# Proiect.net
KiCad netlist of a schematic drawn in EAGLE
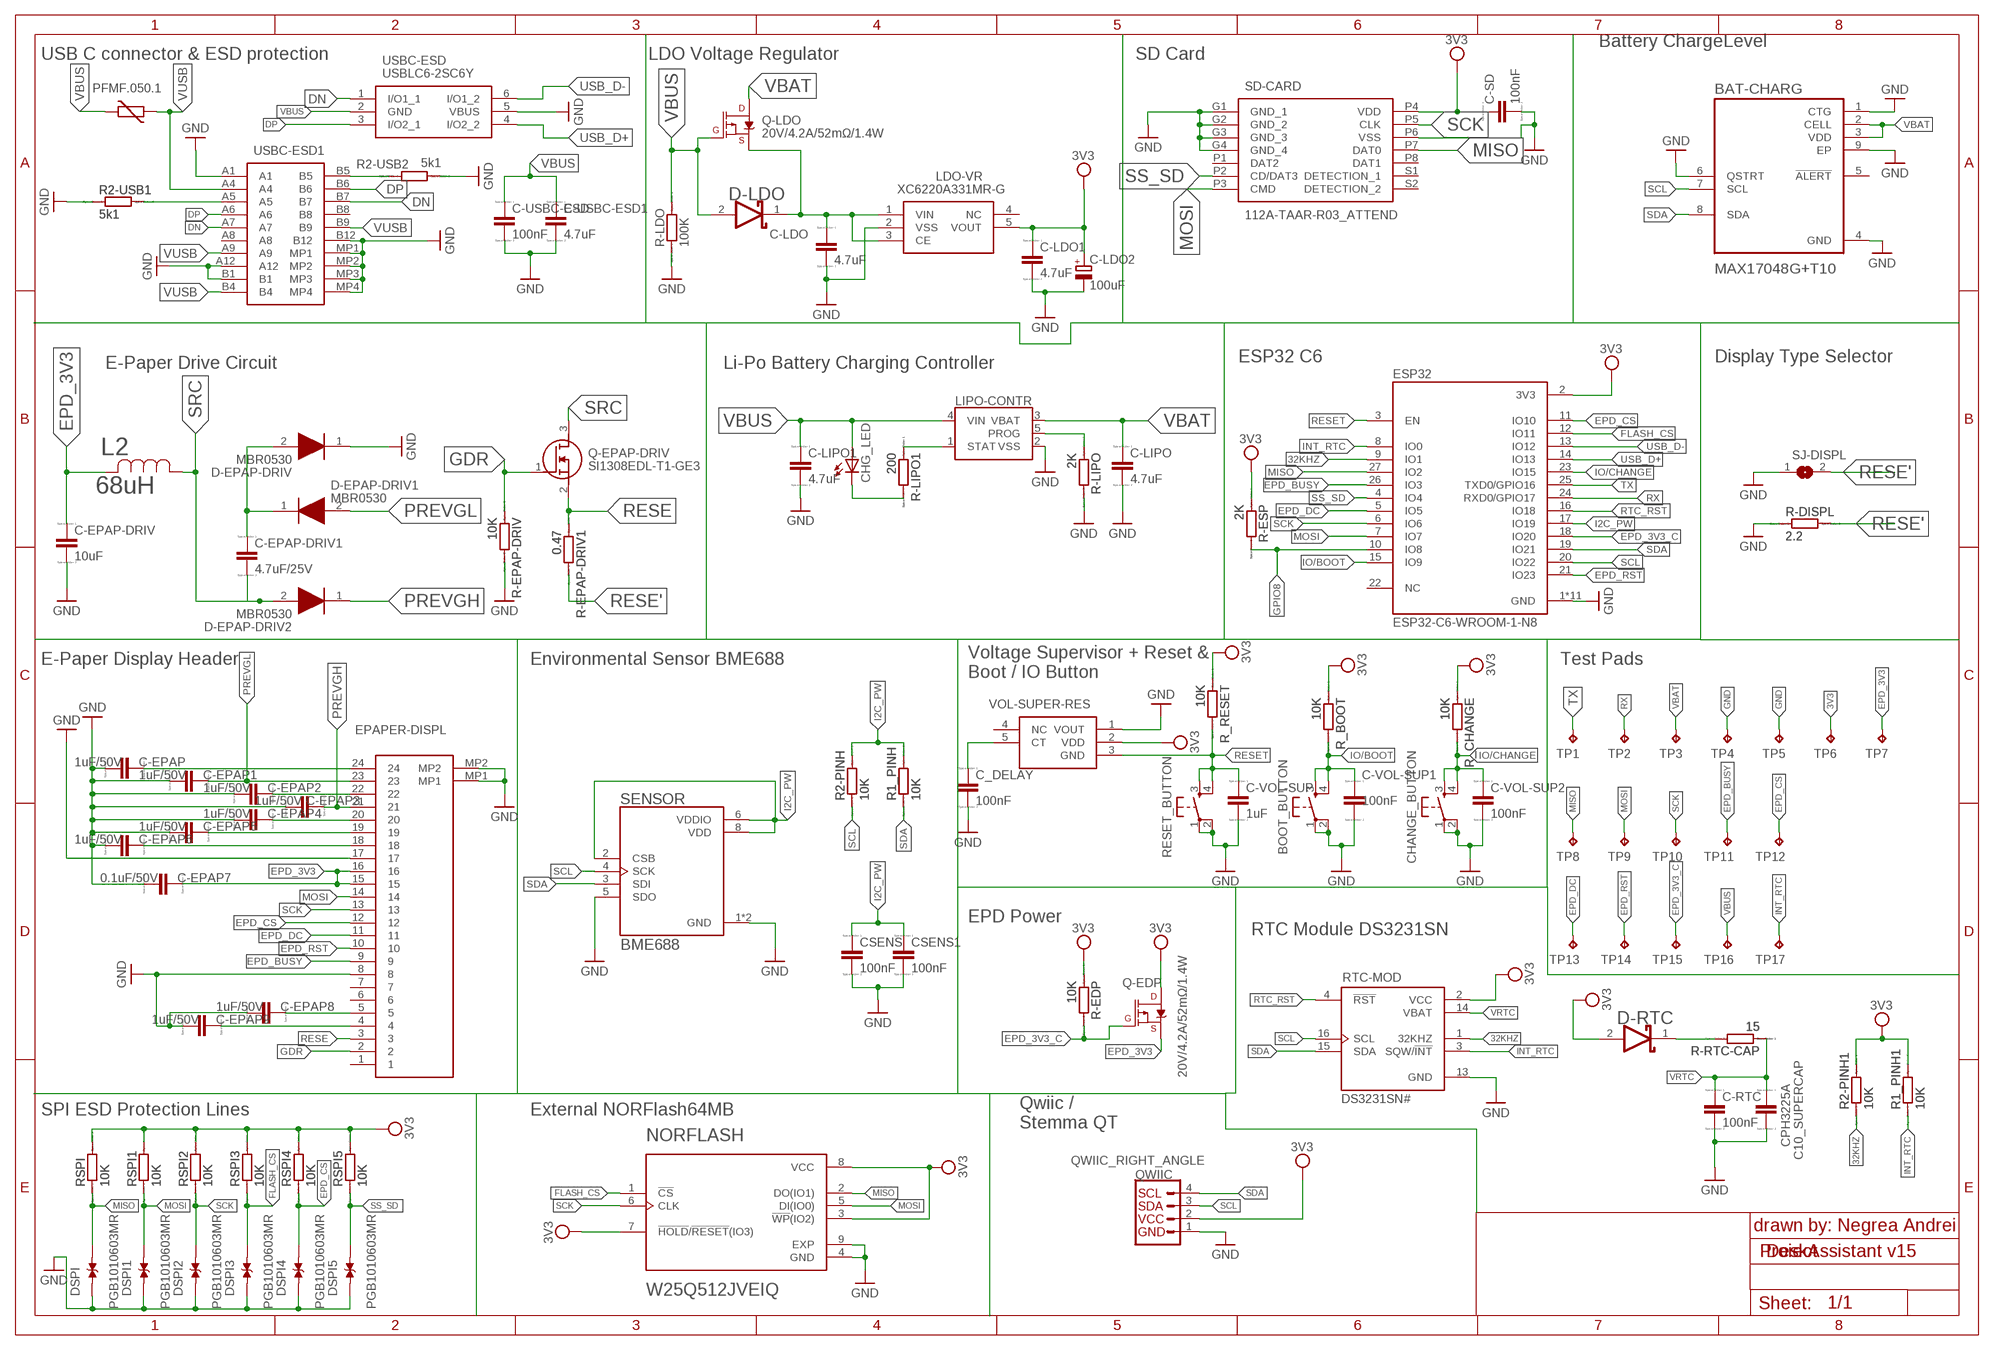
[diagram p0: schematic, sheet 1]

(export (version "E")
  (design (tool "Eeschema 10.0.6"))
  (components
    (comp (ref "BAT-CHARG")
      (value "MAX17048G+T10")
      (footprint "eagle-import:SON50P200X200X80-9N")
      (fields (field (name "MF") "Analog Devices"))
      (libsource (lib "eagle-import") (part "MAX17048G+T10"))
    )
    (comp (ref "BOOT_BUTTON")
      (value "BOOT_BUTTON")
      (footprint "eagle-import:MYBUTTON")
      (libsource (lib "eagle-import") (part "BUTTON_CUSYOMV1"))
    )
    (comp (ref "C-EPAP")
      (value "1uF/50V")
      (footprint "eagle-import:ESP32_WROVER_EAGLE-LTSPICE_C0402")
      (libsource (lib "eagle-import") (part "ESP32_WROVER_EAGLE-LTSPICE_CC0402"))
    )
    (comp (ref "C-EPAP-DRIV")
      (value "10uF")
      (footprint "eagle-import:ESP32_WROVER_EAGLE-LTSPICE_C0402")
      (libsource (lib "eagle-import") (part "ESP32_WROVER_EAGLE-LTSPICE_CC0402"))
    )
    (comp (ref "C-EPAP-DRIV1")
      (value "4.7uF/25V")
      (footprint "eagle-import:ESP32_WROVER_EAGLE-LTSPICE_C0402")
      (libsource (lib "eagle-import") (part "ESP32_WROVER_EAGLE-LTSPICE_CC0402"))
    )
    (comp (ref "C-EPAP1")
      (value "1uF/50V")
      (footprint "eagle-import:ESP32_WROVER_EAGLE-LTSPICE_C0402")
      (libsource (lib "eagle-import") (part "ESP32_WROVER_EAGLE-LTSPICE_CC0402"))
    )
    (comp (ref "C-EPAP2")
      (value "1uF/50V")
      (footprint "eagle-import:ESP32_WROVER_EAGLE-LTSPICE_C0402")
      (libsource (lib "eagle-import") (part "ESP32_WROVER_EAGLE-LTSPICE_CC0402"))
    )
    (comp (ref "C-EPAP3")
      (value "1uF/50V")
      (footprint "eagle-import:ESP32_WROVER_EAGLE-LTSPICE_C0402")
      (libsource (lib "eagle-import") (part "ESP32_WROVER_EAGLE-LTSPICE_CC0402"))
    )
    (comp (ref "C-EPAP4")
      (value "1uF/50V")
      (footprint "eagle-import:ESP32_WROVER_EAGLE-LTSPICE_C0402")
      (libsource (lib "eagle-import") (part "ESP32_WROVER_EAGLE-LTSPICE_CC0402"))
    )
    (comp (ref "C-EPAP5")
      (value "1uF/50V")
      (footprint "eagle-import:ESP32_WROVER_EAGLE-LTSPICE_C0402")
      (libsource (lib "eagle-import") (part "ESP32_WROVER_EAGLE-LTSPICE_CC0402"))
    )
    (comp (ref "C-EPAP6")
      (value "1uF/50V")
      (footprint "eagle-import:ESP32_WROVER_EAGLE-LTSPICE_C0402")
      (libsource (lib "eagle-import") (part "ESP32_WROVER_EAGLE-LTSPICE_CC0402"))
    )
    (comp (ref "C-EPAP7")
      (value "0.1uF/50V")
      (footprint "eagle-import:ESP32_WROVER_EAGLE-LTSPICE_C0402")
      (libsource (lib "eagle-import") (part "ESP32_WROVER_EAGLE-LTSPICE_CC0402"))
    )
    (comp (ref "C-EPAP8")
      (value "1uF/50V")
      (footprint "eagle-import:ESP32_WROVER_EAGLE-LTSPICE_C0402")
      (libsource (lib "eagle-import") (part "ESP32_WROVER_EAGLE-LTSPICE_CC0402"))
    )
    (comp (ref "C-EPAP9")
      (value "1uF/50V")
      (footprint "eagle-import:ESP32_WROVER_EAGLE-LTSPICE_C0402")
      (libsource (lib "eagle-import") (part "ESP32_WROVER_EAGLE-LTSPICE_CC0402"))
    )
    (comp (ref "C-LDO")
      (value "4.7uF")
      (footprint "eagle-import:ESP32_WROVER_EAGLE-LTSPICE_C0402")
      (libsource (lib "eagle-import") (part "ESP32_WROVER_EAGLE-LTSPICE_CC0402"))
    )
    (comp (ref "C-LDO1")
      (value "4.7uF")
      (footprint "eagle-import:ESP32_WROVER_EAGLE-LTSPICE_C0402")
      (libsource (lib "eagle-import") (part "ESP32_WROVER_EAGLE-LTSPICE_CC0402"))
    )
    (comp (ref "C-LDO2")
      (value "100uF")
      (footprint "eagle-import:RCL_CT3528")
      (libsource (lib "eagle-import") (part "RCL_CPOL-EUCT3528"))
    )
    (comp (ref "C-LIPO")
      (value "4.7uF")
      (footprint "eagle-import:ESP32_WROVER_EAGLE-LTSPICE_C0402")
      (libsource (lib "eagle-import") (part "ESP32_WROVER_EAGLE-LTSPICE_CC0402"))
    )
    (comp (ref "C-LIPO1")
      (value "4.7uF")
      (footprint "eagle-import:ESP32_WROVER_EAGLE-LTSPICE_C0402")
      (libsource (lib "eagle-import") (part "ESP32_WROVER_EAGLE-LTSPICE_CC0402"))
    )
    (comp (ref "C-RTC")
      (value "100nF")
      (footprint "eagle-import:ESP32_WROVER_EAGLE-LTSPICE_C0402")
      (libsource (lib "eagle-import") (part "ESP32_WROVER_EAGLE-LTSPICE_CC0402"))
    )
    (comp (ref "C-SD")
      (value "100nF")
      (footprint "eagle-import:ESP32_WROVER_EAGLE-LTSPICE_C0402")
      (libsource (lib "eagle-import") (part "ESP32_WROVER_EAGLE-LTSPICE_CC0402"))
    )
    (comp (ref "C-USBC-ESD")
      (value "100nF")
      (footprint "eagle-import:ESP32_WROVER_EAGLE-LTSPICE_C0402")
      (libsource (lib "eagle-import") (part "ESP32_WROVER_EAGLE-LTSPICE_CC0402"))
    )
    (comp (ref "C-USBC-ESD1")
      (value "4.7uF")
      (footprint "eagle-import:ESP32_WROVER_EAGLE-LTSPICE_C0402")
      (libsource (lib "eagle-import") (part "ESP32_WROVER_EAGLE-LTSPICE_CC0402"))
    )
    (comp (ref "C-VOL-SUP")
      (value "1uF")
      (footprint "eagle-import:ESP32_WROVER_EAGLE-LTSPICE_C0402")
      (libsource (lib "eagle-import") (part "ESP32_WROVER_EAGLE-LTSPICE_CC0402"))
    )
    (comp (ref "C-VOL-SUP1")
      (value "100nF")
      (footprint "eagle-import:ESP32_WROVER_EAGLE-LTSPICE_C0402")
      (libsource (lib "eagle-import") (part "ESP32_WROVER_EAGLE-LTSPICE_CC0402"))
    )
    (comp (ref "C-VOL-SUP2")
      (value "100nF")
      (footprint "eagle-import:ESP32_WROVER_EAGLE-LTSPICE_C0402")
      (libsource (lib "eagle-import") (part "ESP32_WROVER_EAGLE-LTSPICE_CC0402"))
    )
    (comp (ref "CHANGE_BUTTON")
      (value "CHANGE_BUTTON")
      (footprint "eagle-import:MYBUTTON")
      (libsource (lib "eagle-import") (part "BUTTON_CUSYOMV1"))
    )
    (comp (ref "CHG_LED")
      (value "ADAFRUIT_LEDCHIP-LED0603")
      (footprint "eagle-import:ADAFRUIT_CHIP-LED0603")
      (libsource (lib "eagle-import") (part "ADAFRUIT_LEDCHIP-LED0603"))
    )
    (comp (ref "CPH3225A")
      (value "C10_SUPERCAP")
      (footprint "eagle-import:ESP32_WROVER_EAGLE-LTSPICE_C0402")
      (libsource (lib "eagle-import") (part "ESP32_WROVER_EAGLE-LTSPICE_CC0402"))
    )
    (comp (ref "CSENS")
      (value "100nF")
      (footprint "eagle-import:ESP32_WROVER_EAGLE-LTSPICE_C0402")
      (libsource (lib "eagle-import") (part "ESP32_WROVER_EAGLE-LTSPICE_CC0402"))
    )
    (comp (ref "CSENS1")
      (value "100nF")
      (footprint "eagle-import:ESP32_WROVER_EAGLE-LTSPICE_C0402")
      (libsource (lib "eagle-import") (part "ESP32_WROVER_EAGLE-LTSPICE_CC0402"))
    )
    (comp (ref "C_DELAY")
      (value "100nF")
      (footprint "eagle-import:ESP32_WROVER_EAGLE-LTSPICE_C0402")
      (libsource (lib "eagle-import") (part "ESP32_WROVER_EAGLE-LTSPICE_CC0402"))
    )
    (comp (ref "D-EPAP-DRIV")
      (value "MBR0530")
      (footprint "eagle-import:SOD3716X135N")
      (fields (field (name "MF") "ON Semiconductor"))
      (libsource (lib "eagle-import") (part "MBR0530"))
    )
    (comp (ref "D-EPAP-DRIV1")
      (value "MBR0530")
      (footprint "eagle-import:SOD3716X135N")
      (fields (field (name "MF") "ON Semiconductor"))
      (libsource (lib "eagle-import") (part "MBR0530"))
    )
    (comp (ref "D-EPAP-DRIV2")
      (value "MBR0530")
      (footprint "eagle-import:SOD3716X135N")
      (fields (field (name "MF") "ON Semiconductor"))
      (libsource (lib "eagle-import") (part "MBR0530"))
    )
    (comp (ref "D-LDO")
      (value "ESP32_WROVER_AVX---SD0805S020S1R0_AVX_SD0805S020S1R0_0_0AVX_SD0805S020S1R0_0_0")
      (footprint "eagle-import:ESP32_WROVER_AVX---SD0805S020S1R0_AVX_SD0805S020S1R0_0")
      (fields
        (field (name "DIGIKEY_PART_NUMBER") "478-7800-1-ND")
        (field (name "MF") "AVX")
        (field (name "MOUSER_PART_NUMBER") "581-SD0805S020S1R0")
      )
      (libsource (lib "eagle-import") (part "ESP32_WROVER_AVX---SD0805S020S1R0_AVX_SD0805S020S1R0_0_0AVX_SD0805S020S1R0_0_0"))
    )
    (comp (ref "D-RTC")
      (value "ESP32_WROVER_AVX---SD0805S020S1R0_AVX_SD0805S020S1R0_0_0AVX_SD0805S020S1R0_0_0")
      (footprint "eagle-import:ESP32_WROVER_AVX---SD0805S020S1R0_AVX_SD0805S020S1R0_0")
      (fields
        (field (name "DIGIKEY_PART_NUMBER") "478-7800-1-ND")
        (field (name "MF") "AVX")
        (field (name "MOUSER_PART_NUMBER") "581-SD0805S020S1R0")
      )
      (libsource (lib "eagle-import") (part "ESP32_WROVER_AVX---SD0805S020S1R0_AVX_SD0805S020S1R0_0_0AVX_SD0805S020S1R0_0_0"))
    )
    (comp (ref "DSPI")
      (value "PGB1010603MR")
      (footprint "eagle-import:DIOC1608X36N")
      (fields (field (name "MF") "Littelfuse Inc."))
      (libsource (lib "eagle-import") (part "PGB1010603MR"))
    )
    (comp (ref "DSPI1")
      (value "PGB1010603MR")
      (footprint "eagle-import:DIOC1608X36N")
      (fields (field (name "MF") "Littelfuse Inc."))
      (libsource (lib "eagle-import") (part "PGB1010603MR"))
    )
    (comp (ref "DSPI2")
      (value "PGB1010603MR")
      (footprint "eagle-import:DIOC1608X36N")
      (fields (field (name "MF") "Littelfuse Inc."))
      (libsource (lib "eagle-import") (part "PGB1010603MR"))
    )
    (comp (ref "DSPI3")
      (value "PGB1010603MR")
      (footprint "eagle-import:DIOC1608X36N")
      (fields (field (name "MF") "Littelfuse Inc."))
      (libsource (lib "eagle-import") (part "PGB1010603MR"))
    )
    (comp (ref "DSPI4")
      (value "PGB1010603MR")
      (footprint "eagle-import:DIOC1608X36N")
      (fields (field (name "MF") "Littelfuse Inc."))
      (libsource (lib "eagle-import") (part "PGB1010603MR"))
    )
    (comp (ref "DSPI5")
      (value "PGB1010603MR")
      (footprint "eagle-import:DIOC1608X36N")
      (fields (field (name "MF") "Littelfuse Inc."))
      (libsource (lib "eagle-import") (part "PGB1010603MR"))
    )
    (comp (ref "EPAPER-DISPL")
      (value "FH34SRJ-24S-0.5SH_99_")
      (footprint "eagle-import:FH34SRJ24S05SH99")
      (fields
        (field (name "MANUFACTURER_PART_NUMBER") "FH34SRJ-24S-0.5SH(99)")
        (field (name "MOUSER_PART_NUMBER") "798-FH34SRJ24S05SH99")
      )
      (libsource (lib "eagle-import") (part "FH34SRJ-24S-0.5SH_99_"))
    )
    (comp (ref "ESP32")
      (value "ESP32-C6-WROOM-1-N8")
      (footprint "eagle-import:XCVR_ESP32-C6-WROOM-1-N8")
      (fields (field (name "MF") "Espressif Systems"))
      (libsource (lib "eagle-import") (part "ESP32-C6-WROOM-1-N8"))
    )
    (comp (ref "L2")
      (value "68uH")
      (footprint "eagle-import:IND_4828-WE-TPC_WRE")
      (fields
        (field (name "MANUFACTURER_PART_NUMBER") "744043680")
        (field (name "COPYRIGHT") "Copyright (C) 2024 Ultra Librarian. All rights reserved.")
      )
      (libsource (lib "eagle-import") (part "744043680IND_4828-WE-TPC_WRE"))
    )
    (comp (ref "LDO-VR")
      (value "XC6220A331MR-G")
      (footprint "eagle-import:SOT95P280X120-5N")
      (fields (field (name "MOUSER_PART_NUMBER") "865-XC6220A331MR-G"))
      (libsource (lib "eagle-import") (part "XC6220A331MR-G"))
    )
    (comp (ref "LIPO-CONTR")
      (value "ESP32_WROVER_SPARKFUN-IC-POWER_MCP73831")
      (footprint "eagle-import:ESP32_WROVER_SPARKFUN-IC-POWER_SOT23-5")
      (libsource (lib "eagle-import") (part "ESP32_WROVER_SPARKFUN-IC-POWER_MCP73831"))
    )
    (comp (ref "NORFLASH")
      (value "W25Q512JVEIQ")
      (footprint "eagle-import:SON127P600X800X80-9N")
      (fields (field (name "MF") "Winbond Electronics"))
      (libsource (lib "eagle-import") (part "W25Q512JVEIQ"))
    )
    (comp (ref "PFMF.050.1")
      (value "ESP32C6_VARISTORCN1812")
      (footprint "eagle-import:ESP32C6_VARISTOR_CT_CN1812")
      (libsource (lib "eagle-import") (part "ESP32C6_VARISTORCN1812"))
    )
    (comp (ref "Q-EDP")
      (value "20V/4.2A/52mΩ/1.4W")
      (footprint "eagle-import:ESP32_WROVER_SPARKFUN-DISCRETESEMI_SOT23-3")
      (libsource (lib "eagle-import") (part "ESP32_WROVER_SPARKFUN-DISCRETESEMI_MOSFET_PCH-DMG2305UX-7"))
    )
    (comp (ref "Q-EPAP-DRIV")
      (value "SI1308EDL-T1-GE3")
      (footprint "eagle-import:SOT65P210X110-3N")
      (fields (field (name "MF") "Vishay Siliconix"))
      (libsource (lib "eagle-import") (part "SI1308EDL-T1-GE3"))
    )
    (comp (ref "Q-LDO")
      (value "20V/4.2A/52mΩ/1.4W")
      (footprint "eagle-import:ESP32_WROVER_SPARKFUN-DISCRETESEMI_SOT23-3")
      (libsource (lib "eagle-import") (part "ESP32_WROVER_SPARKFUN-DISCRETESEMI_MOSFET_PCH-DMG2305UX-7"))
    )
    (comp (ref "QWIIC")
      (value "QWIIC_RIGHT_ANGLE")
      (footprint "eagle-import:JST04_1MM_RA")
      (libsource (lib "eagle-import") (part "QWIIC_CONNECTORJS-1MM"))
    )
    (comp (ref "R-DISPL")
      (value "2.2")
      (footprint "eagle-import:ESP32_WROVER_EAGLE-LTSPICE_R0402")
      (libsource (lib "eagle-import") (part "ESP32_WROVER_EAGLE-LTSPICE_RR0402"))
    )
    (comp (ref "R-EDP")
      (value "10K")
      (footprint "eagle-import:ESP32_WROVER_EAGLE-LTSPICE_R0402")
      (libsource (lib "eagle-import") (part "ESP32_WROVER_EAGLE-LTSPICE_RR0402"))
    )
    (comp (ref "R-EPAP-DRIV")
      (value "10K")
      (footprint "eagle-import:ESP32_WROVER_EAGLE-LTSPICE_R0402")
      (libsource (lib "eagle-import") (part "ESP32_WROVER_EAGLE-LTSPICE_RR0402"))
    )
    (comp (ref "R-EPAP-DRIV1")
      (value "0.47")
      (footprint "eagle-import:ESP32_WROVER_EAGLE-LTSPICE_R0402")
      (libsource (lib "eagle-import") (part "ESP32_WROVER_EAGLE-LTSPICE_RR0402"))
    )
    (comp (ref "R-ESP")
      (value "2K")
      (footprint "eagle-import:ESP32_WROVER_EAGLE-LTSPICE_R0402")
      (libsource (lib "eagle-import") (part "ESP32_WROVER_EAGLE-LTSPICE_RR0402"))
    )
    (comp (ref "R-LDO")
      (value "100K")
      (footprint "eagle-import:ESP32_WROVER_EAGLE-LTSPICE_R0402")
      (libsource (lib "eagle-import") (part "ESP32_WROVER_EAGLE-LTSPICE_RR0402"))
    )
    (comp (ref "R-LIPO")
      (value "2K")
      (footprint "eagle-import:ESP32_WROVER_EAGLE-LTSPICE_R0402")
      (libsource (lib "eagle-import") (part "ESP32_WROVER_EAGLE-LTSPICE_RR0402"))
    )
    (comp (ref "R-LIPO1")
      (value "200")
      (footprint "eagle-import:ESP32_WROVER_EAGLE-LTSPICE_R0402")
      (libsource (lib "eagle-import") (part "ESP32_WROVER_EAGLE-LTSPICE_RR0402"))
    )
    (comp (ref "R-RTC-CAP")
      (value "15")
      (footprint "eagle-import:ESP32_WROVER_EAGLE-LTSPICE_R0402")
      (libsource (lib "eagle-import") (part "ESP32_WROVER_EAGLE-LTSPICE_RR0402"))
    )
    (comp (ref "R1_PINH")
      (value "10K")
      (footprint "eagle-import:ESP32_WROVER_EAGLE-LTSPICE_R0402")
      (libsource (lib "eagle-import") (part "ESP32_WROVER_EAGLE-LTSPICE_RR0402"))
    )
    (comp (ref "R1_PINH1")
      (value "10K")
      (footprint "eagle-import:ESP32_WROVER_EAGLE-LTSPICE_R0402")
      (libsource (lib "eagle-import") (part "ESP32_WROVER_EAGLE-LTSPICE_RR0402"))
    )
    (comp (ref "R2-PINH")
      (value "10K")
      (footprint "eagle-import:ESP32_WROVER_EAGLE-LTSPICE_R0402")
      (libsource (lib "eagle-import") (part "ESP32_WROVER_EAGLE-LTSPICE_RR0402"))
    )
    (comp (ref "R2-PINH1")
      (value "10K")
      (footprint "eagle-import:ESP32_WROVER_EAGLE-LTSPICE_R0402")
      (libsource (lib "eagle-import") (part "ESP32_WROVER_EAGLE-LTSPICE_RR0402"))
    )
    (comp (ref "R2-USB1")
      (value "5k1")
      (footprint "eagle-import:ESP32_WROVER_EAGLE-LTSPICE_R0402")
      (libsource (lib "eagle-import") (part "ESP32_WROVER_EAGLE-LTSPICE_RR0402"))
    )
    (comp (ref "R2-USB2")
      (value "5k1")
      (footprint "eagle-import:ESP32_WROVER_EAGLE-LTSPICE_R0402")
      (libsource (lib "eagle-import") (part "ESP32_WROVER_EAGLE-LTSPICE_RR0402"))
    )
    (comp (ref "RESET_BUTTON")
      (value "RESET_BUTTON")
      (footprint "eagle-import:MYBUTTON")
      (libsource (lib "eagle-import") (part "BUTTON_CUSYOMV1"))
    )
    (comp (ref "RSPI")
      (value "10K")
      (footprint "eagle-import:ESP32_WROVER_EAGLE-LTSPICE_R0402")
      (libsource (lib "eagle-import") (part "ESP32_WROVER_EAGLE-LTSPICE_RR0402"))
    )
    (comp (ref "RSPI1")
      (value "10K")
      (footprint "eagle-import:ESP32_WROVER_EAGLE-LTSPICE_R0402")
      (libsource (lib "eagle-import") (part "ESP32_WROVER_EAGLE-LTSPICE_RR0402"))
    )
    (comp (ref "RSPI2")
      (value "10K")
      (footprint "eagle-import:ESP32_WROVER_EAGLE-LTSPICE_R0402")
      (libsource (lib "eagle-import") (part "ESP32_WROVER_EAGLE-LTSPICE_RR0402"))
    )
    (comp (ref "RSPI3")
      (value "10K")
      (footprint "eagle-import:ESP32_WROVER_EAGLE-LTSPICE_R0402")
      (libsource (lib "eagle-import") (part "ESP32_WROVER_EAGLE-LTSPICE_RR0402"))
    )
    (comp (ref "RSPI4")
      (value "10K")
      (footprint "eagle-import:ESP32_WROVER_EAGLE-LTSPICE_R0402")
      (libsource (lib "eagle-import") (part "ESP32_WROVER_EAGLE-LTSPICE_RR0402"))
    )
    (comp (ref "RSPI5")
      (value "10K")
      (footprint "eagle-import:ESP32_WROVER_EAGLE-LTSPICE_R0402")
      (libsource (lib "eagle-import") (part "ESP32_WROVER_EAGLE-LTSPICE_RR0402"))
    )
    (comp (ref "RTC-MOD")
      (value "DS3231SN#")
      (footprint "eagle-import:SOIC127P1032X265-16N")
      (fields (field (name "MF") "Analog Devices"))
      (libsource (lib "eagle-import") (part "DS3231SN#"))
    )
    (comp (ref "R_BOOT")
      (value "10K")
      (footprint "eagle-import:ESP32_WROVER_EAGLE-LTSPICE_R0402")
      (libsource (lib "eagle-import") (part "ESP32_WROVER_EAGLE-LTSPICE_RR0402"))
    )
    (comp (ref "R_CHANGE")
      (value "10K")
      (footprint "eagle-import:ESP32_WROVER_EAGLE-LTSPICE_R0402")
      (libsource (lib "eagle-import") (part "ESP32_WROVER_EAGLE-LTSPICE_RR0402"))
    )
    (comp (ref "R_RESET")
      (value "10K")
      (footprint "eagle-import:ESP32_WROVER_EAGLE-LTSPICE_R0402")
      (libsource (lib "eagle-import") (part "ESP32_WROVER_EAGLE-LTSPICE_RR0402"))
    )
    (comp (ref "SD-CARD")
      (value "112A-TAAR-R03_ATTEND")
      (footprint "eagle-import:112ATAARR03ATTEND")
      (fields (field (name "MANUFACTURER_PART_NUMBER") "112A-TAAR-R03 ATTEND"))
      (libsource (lib "eagle-import") (part "112A-TAAR-R03_ATTEND"))
    )
    (comp (ref "SENSOR")
      (value "BME688")
      (footprint "eagle-import:ESP32_WROVER_BME680_PSON80P300X300X100-8N")
      (fields (field (name "MF") "Bosch Sensortec") (field (name "MP") "BME680"))
      (libsource (lib "eagle-import") (part "ESP32_WROVER_BME680_BME680"))
    )
    (comp (ref "SJ-DISPL")
      (value "SJ")
      (footprint "eagle-import:SJ")
      (libsource (lib "eagle-import") (part "SJ"))
    )
    (comp (ref "TP1")
      (value "TPTP20R")
      (footprint "eagle-import:TP20R")
      (libsource (lib "eagle-import") (part "TPTP20R"))
    )
    (comp (ref "TP2")
      (value "TPTP20R")
      (footprint "eagle-import:TP20R")
      (libsource (lib "eagle-import") (part "TPTP20R"))
    )
    (comp (ref "TP3")
      (value "TPTP20R")
      (footprint "eagle-import:TP20R")
      (libsource (lib "eagle-import") (part "TPTP20R"))
    )
    (comp (ref "TP4")
      (value "TPTP20R")
      (footprint "eagle-import:TP20R")
      (libsource (lib "eagle-import") (part "TPTP20R"))
    )
    (comp (ref "TP5")
      (value "TPTP20R")
      (footprint "eagle-import:TP20R")
      (libsource (lib "eagle-import") (part "TPTP20R"))
    )
    (comp (ref "TP6")
      (value "TPTP20R")
      (footprint "eagle-import:TP20R")
      (libsource (lib "eagle-import") (part "TPTP20R"))
    )
    (comp (ref "TP7")
      (value "TPTP20R")
      (footprint "eagle-import:TP20R")
      (libsource (lib "eagle-import") (part "TPTP20R"))
    )
    (comp (ref "TP8")
      (value "TPTP20R")
      (footprint "eagle-import:TP20R")
      (libsource (lib "eagle-import") (part "TPTP20R"))
    )
    (comp (ref "TP9")
      (value "TPTP20R")
      (footprint "eagle-import:TP20R")
      (libsource (lib "eagle-import") (part "TPTP20R"))
    )
    (comp (ref "TP10")
      (value "TPTP20R")
      (footprint "eagle-import:TP20R")
      (libsource (lib "eagle-import") (part "TPTP20R"))
    )
    (comp (ref "TP11")
      (value "TPTP20R")
      (footprint "eagle-import:TP20R")
      (libsource (lib "eagle-import") (part "TPTP20R"))
    )
    (comp (ref "TP12")
      (value "TPTP20R")
      (footprint "eagle-import:TP20R")
      (libsource (lib "eagle-import") (part "TPTP20R"))
    )
    (comp (ref "TP13")
      (value "TPTP20R")
      (footprint "eagle-import:TP20R")
      (libsource (lib "eagle-import") (part "TPTP20R"))
    )
    (comp (ref "TP14")
      (value "TPTP20R")
      (footprint "eagle-import:TP20R")
      (libsource (lib "eagle-import") (part "TPTP20R"))
    )
    (comp (ref "TP15")
      (value "TPTP20R")
      (footprint "eagle-import:TP20R")
      (libsource (lib "eagle-import") (part "TPTP20R"))
    )
    (comp (ref "TP16")
      (value "TPTP20R")
      (footprint "eagle-import:TP20R")
      (libsource (lib "eagle-import") (part "TPTP20R"))
    )
    (comp (ref "TP17")
      (value "TPTP20R")
      (footprint "eagle-import:TP20R")
      (libsource (lib "eagle-import") (part "TPTP20R"))
    )
    (comp (ref "USBC-ESD")
      (value "USBLC6-2SC6Y")
      (footprint "eagle-import:SOT95P280X145-6N")
      (fields (field (name "MF") "STMicroelectronics"))
      (libsource (lib "eagle-import") (part "USBLC6-2SC6Y"))
    )
    (comp (ref "USBC-ESD1")
      (value "SAMACSYS_PARTS_USB4110-GF-A")
      (footprint "eagle-import:SAMACSYS_PARTS_USB4110GFA")
      (fields
        (field (name "MANUFACTURER_PART_NUMBER") "USB4110-GF-A")
        (field (name "MOUSER_PART_NUMBER") "640-USB4110-GF-A")
      )
      (libsource (lib "eagle-import") (part "SAMACSYS_PARTS_USB4110-GF-A"))
    )
    (comp (ref "VOL-SUPER")
      (value "VOL-SUPER-RES")
      (footprint "eagle-import:SOT95P280X125-5N")
      (fields
        (field (name "MANUFACTURER_PART_NUMBER") "BD5229G-TR")
        (field (name "MOUSER_PART_NUMBER") "755-BD5229G-TR")
      )
      (libsource (lib "eagle-import") (part "BD5229G-TR"))
    )
  )
  (nets
    (net (code "1") (name "3V3") (class "Default")
      (node (ref "C-LDO1") (pin "1") (pinfunction "1_1") (pintype "passive"))
      (node (ref "C-LDO2") (pin "+") (pinfunction "+_+") (pintype "passive"))
      (node (ref "C-SD") (pin "1") (pinfunction "1_1") (pintype "passive"))
      (node (ref "D-RTC") (pin "2") (pinfunction "ANODE_2") (pintype "bidirectional"))
      (node (ref "ESP32") (pin "2") (pinfunction "3V3_2") (pintype "power_in"))
      (node (ref "LDO-VR") (pin "5") (pinfunction "VOUT_5") (pintype "bidirectional"))
      (node (ref "NORFLASH") (pin "3") (pinfunction "~{WP}(IO2)_3") (pintype "bidirectional"))
      (node (ref "NORFLASH") (pin "7") (pinfunction "~{HOLD}/~{RESET}(IO3)_7") (pintype "bidirectional"))
      (node (ref "NORFLASH") (pin "8") (pinfunction "VCC_8") (pintype "power_in"))
      (node (ref "Q-EDP") (pin "3") (pinfunction "D_3") (pintype "bidirectional"))
      (node (ref "QWIIC") (pin "2") (pinfunction "2_2") (pintype "power_in"))
      (node (ref "R-EDP") (pin "1") (pinfunction "1_1") (pintype "passive"))
      (node (ref "R-ESP") (pin "1") (pinfunction "1_1") (pintype "passive"))
      (node (ref "R1_PINH1") (pin "2") (pinfunction "2_2") (pintype "passive"))
      (node (ref "R2-PINH1") (pin "2") (pinfunction "2_2") (pintype "passive"))
      (node (ref "RSPI") (pin "2") (pinfunction "2_2") (pintype "passive"))
      (node (ref "RSPI1") (pin "2") (pinfunction "2_2") (pintype "passive"))
      (node (ref "RSPI2") (pin "2") (pinfunction "2_2") (pintype "passive"))
      (node (ref "RSPI3") (pin "2") (pinfunction "2_2") (pintype "passive"))
      (node (ref "RSPI4") (pin "2") (pinfunction "2_2") (pintype "passive"))
      (node (ref "RSPI5") (pin "2") (pinfunction "2_2") (pintype "passive"))
      (node (ref "RTC-MOD") (pin "2") (pinfunction "VCC_2") (pintype "power_in"))
      (node (ref "R_BOOT") (pin "1") (pinfunction "1_1") (pintype "passive"))
      (node (ref "R_CHANGE") (pin "1") (pinfunction "1_1") (pintype "passive"))
      (node (ref "R_RESET") (pin "1") (pinfunction "1_1") (pintype "passive"))
      (node (ref "SD-CARD") (pin "P4") (pinfunction "VDD_P4") (pintype "bidirectional"))
      (node (ref "TP6") (pin "TP") (pinfunction "TP_TP") (pintype "input"))
      (node (ref "VOL-SUPER") (pin "2") (pinfunction "VDD_2") (pintype "bidirectional"))
    )
    (net (code "2") (name "32KHZ") (class "Default")
      (node (ref "ESP32") (pin "9") (pinfunction "IO1_9") (pintype "bidirectional"))
      (node (ref "R2-PINH1") (pin "1") (pinfunction "1_1") (pintype "passive"))
      (node (ref "RTC-MOD") (pin "1") (pinfunction "32KHZ_1") (pintype "output"))
    )
    (net (code "3") (name "DN") (class "Default")
      (node (ref "USBC-ESD") (pin "1") (pinfunction "I/O1_1_1") (pintype "bidirectional"))
      (node (ref "USBC-ESD1") (pin "A7") (pinfunction "A7_A7") (pintype "bidirectional"))
      (node (ref "USBC-ESD1") (pin "B7") (pinfunction "B7_B7") (pintype "bidirectional"))
    )
    (net (code "4") (name "DP") (class "Default")
      (node (ref "USBC-ESD") (pin "3") (pinfunction "I/O2_1_3") (pintype "bidirectional"))
      (node (ref "USBC-ESD1") (pin "A6") (pinfunction "A6_A6") (pintype "bidirectional"))
      (node (ref "USBC-ESD1") (pin "B6") (pinfunction "B6_B6") (pintype "bidirectional"))
    )
    (net (code "5") (name "EPD_3V3") (class "Default")
      (node (ref "C-EPAP-DRIV") (pin "1") (pinfunction "1_1") (pintype "passive"))
      (node (ref "C-EPAP7") (pin "1") (pinfunction "1_1") (pintype "passive"))
      (node (ref "EPAPER-DISPL") (pin "15") (pinfunction "15_15") (pintype "bidirectional"))
      (node (ref "EPAPER-DISPL") (pin "16") (pinfunction "16_16") (pintype "bidirectional"))
      (node (ref "L2") (pin "2") (pinfunction "2_2") (pintype "passive"))
      (node (ref "Q-EDP") (pin "2") (pinfunction "S_2") (pintype "bidirectional"))
      (node (ref "TP7") (pin "TP") (pinfunction "TP_TP") (pintype "input"))
    )
    (net (code "6") (name "EPD_3V3_C") (class "Default")
      (node (ref "ESP32") (pin "18") (pinfunction "IO20_18") (pintype "bidirectional"))
      (node (ref "Q-EDP") (pin "1") (pinfunction "G_1") (pintype "bidirectional"))
      (node (ref "R-EDP") (pin "2") (pinfunction "2_2") (pintype "passive"))
      (node (ref "TP15") (pin "TP") (pinfunction "TP_TP") (pintype "input"))
    )
    (net (code "7") (name "EPD_BUSY") (class "Default")
      (node (ref "EPAPER-DISPL") (pin "9") (pinfunction "9_9") (pintype "bidirectional"))
      (node (ref "ESP32") (pin "26") (pinfunction "IO3_26") (pintype "bidirectional"))
      (node (ref "TP11") (pin "TP") (pinfunction "TP_TP") (pintype "input"))
    )
    (net (code "8") (name "EPD_CS") (class "Default")
      (node (ref "DSPI4") (pin "2") (pinfunction "2_2") (pintype "passive"))
      (node (ref "EPAPER-DISPL") (pin "12") (pinfunction "12_12") (pintype "bidirectional"))
      (node (ref "ESP32") (pin "11") (pinfunction "IO10_11") (pintype "bidirectional"))
      (node (ref "RSPI4") (pin "1") (pinfunction "1_1") (pintype "passive"))
      (node (ref "TP12") (pin "TP") (pinfunction "TP_TP") (pintype "input"))
    )
    (net (code "9") (name "EPD_DC") (class "Default")
      (node (ref "EPAPER-DISPL") (pin "11") (pinfunction "11_11") (pintype "bidirectional"))
      (node (ref "ESP32") (pin "5") (pinfunction "IO5_5") (pintype "bidirectional"))
      (node (ref "TP13") (pin "TP") (pinfunction "TP_TP") (pintype "input"))
    )
    (net (code "10") (name "EPD_RST") (class "Default")
      (node (ref "EPAPER-DISPL") (pin "10") (pinfunction "10_10") (pintype "bidirectional"))
      (node (ref "ESP32") (pin "21") (pinfunction "IO23_21") (pintype "bidirectional"))
      (node (ref "TP14") (pin "TP") (pinfunction "TP_TP") (pintype "input"))
    )
    (net (code "11") (name "FLASH_CS") (class "Default")
      (node (ref "DSPI3") (pin "2") (pinfunction "2_2") (pintype "passive"))
      (node (ref "ESP32") (pin "12") (pinfunction "IO11_12") (pintype "bidirectional"))
      (node (ref "NORFLASH") (pin "1") (pinfunction "~{CS}_1") (pintype "input"))
      (node (ref "RSPI3") (pin "1") (pinfunction "1_1") (pintype "passive"))
    )
    (net (code "12") (name "GDR") (class "Default")
      (node (ref "EPAPER-DISPL") (pin "2") (pinfunction "2_2") (pintype "bidirectional"))
      (node (ref "Q-EPAP-DRIV") (pin "1") (pinfunction "G_1") (pintype "bidirectional"))
      (node (ref "R-EPAP-DRIV") (pin "1") (pinfunction "1_1") (pintype "passive"))
    )
    (net (code "13") (name "GND") (class "Default")
      (node (ref "BAT-CHARG") (pin "1") (pinfunction "CTG_1") (pintype "power_in"))
      (node (ref "BAT-CHARG") (pin "4") (pinfunction "GND_4") (pintype "power_in"))
      (node (ref "BAT-CHARG") (pin "6") (pinfunction "QSTRT_6") (pintype "input"))
      (node (ref "BAT-CHARG") (pin "9") (pinfunction "EP_9") (pintype "power_in"))
      (node (ref "BOOT_BUTTON") (pin "1") (pinfunction "1_1") (pintype "passive"))
      (node (ref "BOOT_BUTTON") (pin "2") (pinfunction "2_2") (pintype "passive"))
      (node (ref "C-EPAP") (pin "2") (pinfunction "2_2") (pintype "passive"))
      (node (ref "C-EPAP-DRIV") (pin "2") (pinfunction "2_2") (pintype "passive"))
      (node (ref "C-EPAP1") (pin "2") (pinfunction "2_2") (pintype "passive"))
      (node (ref "C-EPAP2") (pin "2") (pinfunction "2_2") (pintype "passive"))
      (node (ref "C-EPAP3") (pin "2") (pinfunction "2_2") (pintype "passive"))
      (node (ref "C-EPAP4") (pin "2") (pinfunction "2_2") (pintype "passive"))
      (node (ref "C-EPAP5") (pin "2") (pinfunction "2_2") (pintype "passive"))
      (node (ref "C-EPAP6") (pin "2") (pinfunction "2_2") (pintype "passive"))
      (node (ref "C-EPAP7") (pin "2") (pinfunction "2_2") (pintype "passive"))
      (node (ref "C-EPAP8") (pin "2") (pinfunction "2_2") (pintype "passive"))
      (node (ref "C-EPAP9") (pin "2") (pinfunction "2_2") (pintype "passive"))
      (node (ref "C-LDO") (pin "2") (pinfunction "2_2") (pintype "passive"))
      (node (ref "C-LDO1") (pin "2") (pinfunction "2_2") (pintype "passive"))
      (node (ref "C-LDO2") (pin "-") (pinfunction "-_-") (pintype "passive"))
      (node (ref "C-LIPO") (pin "2") (pinfunction "2_2") (pintype "passive"))
      (node (ref "C-LIPO1") (pin "2") (pinfunction "2_2") (pintype "passive"))
      (node (ref "C-RTC") (pin "2") (pinfunction "2_2") (pintype "passive"))
      (node (ref "C-SD") (pin "2") (pinfunction "2_2") (pintype "passive"))
      (node (ref "C-USBC-ESD") (pin "2") (pinfunction "2_2") (pintype "passive"))
      (node (ref "C-USBC-ESD1") (pin "2") (pinfunction "2_2") (pintype "passive"))
      (node (ref "C-VOL-SUP") (pin "2") (pinfunction "2_2") (pintype "passive"))
      (node (ref "C-VOL-SUP1") (pin "2") (pinfunction "2_2") (pintype "passive"))
      (node (ref "C-VOL-SUP2") (pin "2") (pinfunction "2_2") (pintype "passive"))
      (node (ref "CHANGE_BUTTON") (pin "1") (pinfunction "1_1") (pintype "passive"))
      (node (ref "CHANGE_BUTTON") (pin "2") (pinfunction "2_2") (pintype "passive"))
      (node (ref "CPH3225A") (pin "2") (pinfunction "2_2") (pintype "passive"))
      (node (ref "CSENS") (pin "2") (pinfunction "2_2") (pintype "passive"))
      (node (ref "CSENS1") (pin "2") (pinfunction "2_2") (pintype "passive"))
      (node (ref "C_DELAY") (pin "2") (pinfunction "2_2") (pintype "passive"))
      (node (ref "D-EPAP-DRIV") (pin "1") (pinfunction "K_1") (pintype "bidirectional"))
      (node (ref "DSPI") (pin "1") (pinfunction "1_1") (pintype "passive"))
      (node (ref "DSPI1") (pin "1") (pinfunction "1_1") (pintype "passive"))
      (node (ref "DSPI2") (pin "1") (pinfunction "1_1") (pintype "passive"))
      (node (ref "DSPI3") (pin "1") (pinfunction "1_1") (pintype "passive"))
      (node (ref "DSPI4") (pin "1") (pinfunction "1_1") (pintype "passive"))
      (node (ref "DSPI5") (pin "1") (pinfunction "1_1") (pintype "passive"))
      (node (ref "EPAPER-DISPL") (pin "17") (pinfunction "17_17") (pintype "bidirectional"))
      (node (ref "EPAPER-DISPL") (pin "8") (pinfunction "8_8") (pintype "bidirectional"))
      (node (ref "EPAPER-DISPL") (pin "MP1") (pinfunction "MP1_MP1") (pintype "bidirectional"))
      (node (ref "EPAPER-DISPL") (pin "MP2") (pinfunction "MP2_MP2") (pintype "bidirectional"))
      (node (ref "ESP32") (pin "1") (pinfunction "GND_1") (pintype "power_in"))
      (node (ref "ESP32") (pin "28") (pinfunction "GND_28") (pintype "power_in"))
      (node (ref "ESP32") (pin "29_1") (pinfunction "GND_29_1") (pintype "power_in"))
      (node (ref "ESP32") (pin "29_2") (pinfunction "GND_29_2") (pintype "power_in"))
      (node (ref "ESP32") (pin "29_3") (pinfunction "GND_29_3") (pintype "power_in"))
      (node (ref "ESP32") (pin "29_4") (pinfunction "GND_29_4") (pintype "power_in"))
      (node (ref "ESP32") (pin "29_5") (pinfunction "GND_29_5") (pintype "power_in"))
      (node (ref "ESP32") (pin "29_6") (pinfunction "GND_29_6") (pintype "power_in"))
      (node (ref "ESP32") (pin "29_7") (pinfunction "GND_29_7") (pintype "power_in"))
      (node (ref "ESP32") (pin "29_8") (pinfunction "GND_29_8") (pintype "power_in"))
      (node (ref "ESP32") (pin "29_9") (pinfunction "GND_29_9") (pintype "power_in"))
      (node (ref "LDO-VR") (pin "2") (pinfunction "VSS_2") (pintype "bidirectional"))
      (node (ref "LIPO-CONTR") (pin "2") (pinfunction "VSS_2") (pintype "power_in"))
      (node (ref "NORFLASH") (pin "4") (pinfunction "GND_4") (pintype "power_in"))
      (node (ref "NORFLASH") (pin "9") (pinfunction "EXP_9") (pintype "passive"))
      (node (ref "QWIIC") (pin "1") (pinfunction "1_1") (pintype "power_in"))
      (node (ref "R-DISPL") (pin "1") (pinfunction "1_1") (pintype "passive"))
      (node (ref "R-EPAP-DRIV") (pin "2") (pinfunction "2_2") (pintype "passive"))
      (node (ref "R-LDO") (pin "1") (pinfunction "1_1") (pintype "passive"))
      (node (ref "R-LIPO") (pin "2") (pinfunction "2_2") (pintype "passive"))
      (node (ref "R2-USB1") (pin "1") (pinfunction "1_1") (pintype "passive"))
      (node (ref "R2-USB2") (pin "2") (pinfunction "2_2") (pintype "passive"))
      (node (ref "RESET_BUTTON") (pin "1") (pinfunction "1_1") (pintype "passive"))
      (node (ref "RESET_BUTTON") (pin "2") (pinfunction "2_2") (pintype "passive"))
      (node (ref "RTC-MOD") (pin "13") (pinfunction "GND_13") (pintype "power_in"))
      (node (ref "SD-CARD") (pin "G1") (pinfunction "GND_1_G1") (pintype "bidirectional"))
      (node (ref "SD-CARD") (pin "G2") (pinfunction "GND_2_G2") (pintype "bidirectional"))
      (node (ref "SD-CARD") (pin "G3") (pinfunction "GND_3_G3") (pintype "bidirectional"))
      (node (ref "SD-CARD") (pin "G4") (pinfunction "GND_4_G4") (pintype "bidirectional"))
      (node (ref "SD-CARD") (pin "P6") (pinfunction "VSS_P6") (pintype "bidirectional"))
      (node (ref "SENSOR") (pin "1") (pinfunction "GND_1") (pintype "power_in"))
      (node (ref "SENSOR") (pin "5") (pinfunction "SDO_5") (pintype "bidirectional"))
      (node (ref "SENSOR") (pin "7") (pinfunction "GND_7") (pintype "power_in"))
      (node (ref "SJ-DISPL") (pin "1") (pinfunction "1_1") (pintype "passive"))
      (node (ref "TP4") (pin "TP") (pinfunction "TP_TP") (pintype "input"))
      (node (ref "TP5") (pin "TP") (pinfunction "TP_TP") (pintype "input"))
      (node (ref "USBC-ESD") (pin "5") (pinfunction "VBUS_5") (pintype "bidirectional"))
      (node (ref "USBC-ESD1") (pin "A1") (pinfunction "A1_A1") (pintype "bidirectional"))
      (node (ref "USBC-ESD1") (pin "A12") (pinfunction "A12_A12") (pintype "bidirectional"))
      (node (ref "USBC-ESD1") (pin "B1") (pinfunction "B1_B1") (pintype "bidirectional"))
      (node (ref "USBC-ESD1") (pin "B12") (pinfunction "B12_B12") (pintype "bidirectional"))
      (node (ref "USBC-ESD1") (pin "MP1") (pinfunction "MP1_MP1") (pintype "bidirectional"))
      (node (ref "USBC-ESD1") (pin "MP2") (pinfunction "MP2_MP2") (pintype "bidirectional"))
      (node (ref "USBC-ESD1") (pin "MP3") (pinfunction "MP3_MP3") (pintype "bidirectional"))
      (node (ref "USBC-ESD1") (pin "MP4") (pinfunction "MP4_MP4") (pintype "bidirectional"))
      (node (ref "VOL-SUPER") (pin "1") (pinfunction "VOUT_1") (pintype "bidirectional"))
    )
    (net (code "14") (name "GPIO8") (class "Default")
      (node (ref "ESP32") (pin "10") (pinfunction "IO8_10") (pintype "bidirectional"))
      (node (ref "R-ESP") (pin "2") (pinfunction "2_2") (pintype "passive"))
    )
    (net (code "15") (name "I2C_PW") (class "Default")
      (node (ref "CSENS") (pin "1") (pinfunction "1_1") (pintype "passive"))
      (node (ref "CSENS1") (pin "1") (pinfunction "1_1") (pintype "passive"))
      (node (ref "ESP32") (pin "17") (pinfunction "IO19_17") (pintype "bidirectional"))
      (node (ref "R1_PINH") (pin "2") (pinfunction "2_2") (pintype "passive"))
      (node (ref "R2-PINH") (pin "2") (pinfunction "2_2") (pintype "passive"))
      (node (ref "SENSOR") (pin "2") (pinfunction "CSB_2") (pintype "input"))
      (node (ref "SENSOR") (pin "6") (pinfunction "VDDIO_6") (pintype "power_in"))
      (node (ref "SENSOR") (pin "8") (pinfunction "VDD_8") (pintype "power_in"))
    )
    (net (code "16") (name "INT_RTC") (class "Default")
      (node (ref "ESP32") (pin "8") (pinfunction "IO0_8") (pintype "bidirectional"))
      (node (ref "R1_PINH1") (pin "1") (pinfunction "1_1") (pintype "passive"))
      (node (ref "RTC-MOD") (pin "3") (pinfunction "SQW/~{INT}_3") (pintype "output"))
      (node (ref "TP17") (pin "TP") (pinfunction "TP_TP") (pintype "input"))
    )
    (net (code "17") (name "IO{slash}BOOT") (class "Default")
      (node (ref "BOOT_BUTTON") (pin "3") (pinfunction "3_3") (pintype "passive"))
      (node (ref "BOOT_BUTTON") (pin "4") (pinfunction "4_4") (pintype "passive"))
      (node (ref "C-VOL-SUP1") (pin "1") (pinfunction "1_1") (pintype "passive"))
      (node (ref "ESP32") (pin "15") (pinfunction "IO9_15") (pintype "bidirectional"))
      (node (ref "R_BOOT") (pin "2") (pinfunction "2_2") (pintype "passive"))
    )
    (net (code "18") (name "IO{slash}CHANGE") (class "Default")
      (node (ref "C-VOL-SUP2") (pin "1") (pinfunction "1_1") (pintype "passive"))
      (node (ref "CHANGE_BUTTON") (pin "3") (pinfunction "3_3") (pintype "passive"))
      (node (ref "CHANGE_BUTTON") (pin "4") (pinfunction "4_4") (pintype "passive"))
      (node (ref "ESP32") (pin "23") (pinfunction "IO15_23") (pintype "bidirectional"))
      (node (ref "R_CHANGE") (pin "2") (pinfunction "2_2") (pintype "passive"))
    )
    (net (code "19") (name "MISO") (class "Default")
      (node (ref "DSPI") (pin "2") (pinfunction "2_2") (pintype "passive"))
      (node (ref "ESP32") (pin "27") (pinfunction "IO2_27") (pintype "bidirectional"))
      (node (ref "NORFLASH") (pin "2") (pinfunction "DO(IO1)_2") (pintype "bidirectional"))
      (node (ref "RSPI") (pin "1") (pinfunction "1_1") (pintype "passive"))
      (node (ref "SD-CARD") (pin "P7") (pinfunction "DAT0_P7") (pintype "bidirectional"))
      (node (ref "TP8") (pin "TP") (pinfunction "TP_TP") (pintype "input"))
    )
    (net (code "20") (name "MOSI") (class "Default")
      (node (ref "DSPI1") (pin "2") (pinfunction "2_2") (pintype "passive"))
      (node (ref "EPAPER-DISPL") (pin "14") (pinfunction "14_14") (pintype "bidirectional"))
      (node (ref "ESP32") (pin "7") (pinfunction "IO7_7") (pintype "bidirectional"))
      (node (ref "NORFLASH") (pin "5") (pinfunction "DI(IO0)_5") (pintype "bidirectional"))
      (node (ref "RSPI1") (pin "1") (pinfunction "1_1") (pintype "passive"))
      (node (ref "SD-CARD") (pin "P3") (pinfunction "CMD_P3") (pintype "bidirectional"))
      (node (ref "TP9") (pin "TP") (pinfunction "TP_TP") (pintype "input"))
    )
    (net (code "21") (name "Net-(C-EPAP-Pad1)") (class "Default")
      (node (ref "C-EPAP") (pin "1") (pinfunction "1_1") (pintype "passive"))
      (node (ref "EPAPER-DISPL") (pin "24") (pinfunction "24_24") (pintype "bidirectional"))
    )
    (net (code "22") (name "Net-(C-EPAP2-Pad1)") (class "Default")
      (node (ref "C-EPAP2") (pin "1") (pinfunction "1_1") (pintype "passive"))
      (node (ref "EPAPER-DISPL") (pin "22") (pinfunction "22_22") (pintype "bidirectional"))
    )
    (net (code "23") (name "Net-(C-EPAP4-Pad1)") (class "Default")
      (node (ref "C-EPAP4") (pin "1") (pinfunction "1_1") (pintype "passive"))
      (node (ref "EPAPER-DISPL") (pin "20") (pinfunction "20_20") (pintype "bidirectional"))
    )
    (net (code "24") (name "Net-(C-EPAP5-Pad1)") (class "Default")
      (node (ref "C-EPAP5") (pin "1") (pinfunction "1_1") (pintype "passive"))
      (node (ref "EPAPER-DISPL") (pin "19") (pinfunction "19_19") (pintype "bidirectional"))
    )
    (net (code "25") (name "Net-(C-EPAP6-Pad1)") (class "Default")
      (node (ref "C-EPAP6") (pin "1") (pinfunction "1_1") (pintype "passive"))
      (node (ref "EPAPER-DISPL") (pin "18") (pinfunction "18_18") (pintype "bidirectional"))
    )
    (net (code "26") (name "Net-(C-EPAP8-Pad1)") (class "Default")
      (node (ref "C-EPAP8") (pin "1") (pinfunction "1_1") (pintype "passive"))
      (node (ref "EPAPER-DISPL") (pin "5") (pinfunction "5_5") (pintype "bidirectional"))
    )
    (net (code "27") (name "Net-(C-EPAP9-Pad1)") (class "Default")
      (node (ref "C-EPAP9") (pin "1") (pinfunction "1_1") (pintype "passive"))
      (node (ref "EPAPER-DISPL") (pin "4") (pinfunction "4_4") (pintype "bidirectional"))
    )
    (net (code "28") (name "Net-(CHG_LED-PadC)") (class "Default")
      (node (ref "CHG_LED") (pin "C") (pinfunction "C_C") (pintype "passive"))
      (node (ref "R-LIPO1") (pin "2") (pinfunction "2_2") (pintype "passive"))
    )
    (net (code "29") (name "Net-(D-EPAP-DRIV-A)") (class "Default")
      (node (ref "C-EPAP-DRIV1") (pin "1") (pinfunction "1_1") (pintype "passive"))
      (node (ref "D-EPAP-DRIV") (pin "2") (pinfunction "A_2") (pintype "bidirectional"))
      (node (ref "D-EPAP-DRIV1") (pin "1") (pinfunction "K_1") (pintype "bidirectional"))
    )
    (net (code "30") (name "Net-(D-LDO-CATHODE)") (class "Default")
      (node (ref "C-LDO") (pin "1") (pinfunction "1_1") (pintype "passive"))
      (node (ref "D-LDO") (pin "1") (pinfunction "CATHODE_1") (pintype "bidirectional"))
      (node (ref "LDO-VR") (pin "1") (pinfunction "VIN_1") (pintype "bidirectional"))
      (node (ref "LDO-VR") (pin "3") (pinfunction "CE_3") (pintype "bidirectional"))
      (node (ref "Q-LDO") (pin "2") (pinfunction "S_2") (pintype "bidirectional"))
    )
    (net (code "31") (name "Net-(D-RTC-CATHODE)") (class "Default")
      (node (ref "D-RTC") (pin "1") (pinfunction "CATHODE_1") (pintype "bidirectional"))
      (node (ref "R-RTC-CAP") (pin "2") (pinfunction "2_2") (pintype "passive"))
    )
    (net (code "32") (name "Net-(LIPO-CONTR-PROG)") (class "Default")
      (node (ref "LIPO-CONTR") (pin "5") (pinfunction "PROG_5") (pintype "input"))
      (node (ref "R-LIPO") (pin "1") (pinfunction "1_1") (pintype "passive"))
    )
    (net (code "33") (name "Net-(LIPO-CONTR-STAT)") (class "Default")
      (node (ref "LIPO-CONTR") (pin "1") (pinfunction "STAT_1") (pintype "output"))
      (node (ref "R-LIPO1") (pin "1") (pinfunction "1_1") (pintype "passive"))
    )
    (net (code "34") (name "Net-(R2-USB1-Pad2)") (class "Default")
      (node (ref "R2-USB1") (pin "2") (pinfunction "2_2") (pintype "passive"))
      (node (ref "USBC-ESD1") (pin "A5") (pinfunction "A5_A5") (pintype "bidirectional"))
    )
    (net (code "35") (name "Net-(R2-USB2-Pad1)") (class "Default")
      (node (ref "R2-USB2") (pin "1") (pinfunction "1_1") (pintype "passive"))
      (node (ref "USBC-ESD1") (pin "B5") (pinfunction "B5_B5") (pintype "bidirectional"))
    )
    (net (code "36") (name "Net-(VOL-SUPER-CT)") (class "Default")
      (node (ref "C_DELAY") (pin "1") (pinfunction "1_1") (pintype "passive"))
      (node (ref "VOL-SUPER") (pin "5") (pinfunction "CT_5") (pintype "bidirectional"))
    )
    (net (code "37") (name "PREVGH") (class "Default")
      (node (ref "C-EPAP3") (pin "1") (pinfunction "1_1") (pintype "passive"))
      (node (ref "D-EPAP-DRIV2") (pin "1") (pinfunction "K_1") (pintype "bidirectional"))
      (node (ref "EPAPER-DISPL") (pin "21") (pinfunction "21_21") (pintype "bidirectional"))
    )
    (net (code "38") (name "PREVGL") (class "Default")
      (node (ref "C-EPAP1") (pin "1") (pinfunction "1_1") (pintype "passive"))
      (node (ref "D-EPAP-DRIV1") (pin "2") (pinfunction "A_2") (pintype "bidirectional"))
      (node (ref "EPAPER-DISPL") (pin "23") (pinfunction "23_23") (pintype "bidirectional"))
    )
    (net (code "39") (name "RESE") (class "Default")
      (node (ref "EPAPER-DISPL") (pin "3") (pinfunction "3_3") (pintype "bidirectional"))
      (node (ref "Q-EPAP-DRIV") (pin "2") (pinfunction "S_2") (pintype "bidirectional"))
      (node (ref "R-EPAP-DRIV1") (pin "1") (pinfunction "1_1") (pintype "passive"))
    )
    (net (code "40") (name "RESE'") (class "Default")
      (node (ref "R-DISPL") (pin "2") (pinfunction "2_2") (pintype "passive"))
      (node (ref "R-EPAP-DRIV1") (pin "2") (pinfunction "2_2") (pintype "passive"))
      (node (ref "SJ-DISPL") (pin "2") (pinfunction "2_2") (pintype "passive"))
    )
    (net (code "41") (name "RESET") (class "Default")
      (node (ref "C-VOL-SUP") (pin "1") (pinfunction "1_1") (pintype "passive"))
      (node (ref "ESP32") (pin "3") (pinfunction "EN_3") (pintype "input"))
      (node (ref "RESET_BUTTON") (pin "3") (pinfunction "3_3") (pintype "passive"))
      (node (ref "RESET_BUTTON") (pin "4") (pinfunction "4_4") (pintype "passive"))
      (node (ref "R_RESET") (pin "2") (pinfunction "2_2") (pintype "passive"))
      (node (ref "VOL-SUPER") (pin "3") (pinfunction "GND_3") (pintype "bidirectional"))
    )
    (net (code "42") (name "RTC_RST") (class "Default")
      (node (ref "ESP32") (pin "16") (pinfunction "IO18_16") (pintype "bidirectional"))
      (node (ref "RTC-MOD") (pin "4") (pinfunction "~{RST}_4") (pintype "input"))
    )
    (net (code "43") (name "RX") (class "Default")
      (node (ref "ESP32") (pin "24") (pinfunction "RXD0/GPIO17_24") (pintype "bidirectional"))
      (node (ref "TP2") (pin "TP") (pinfunction "TP_TP") (pintype "input"))
    )
    (net (code "44") (name "SCK") (class "Default")
      (node (ref "DSPI2") (pin "2") (pinfunction "2_2") (pintype "passive"))
      (node (ref "EPAPER-DISPL") (pin "13") (pinfunction "13_13") (pintype "bidirectional"))
      (node (ref "ESP32") (pin "6") (pinfunction "IO6_6") (pintype "bidirectional"))
      (node (ref "NORFLASH") (pin "6") (pinfunction "CLK_6") (pintype "input"))
      (node (ref "RSPI2") (pin "1") (pinfunction "1_1") (pintype "passive"))
      (node (ref "SD-CARD") (pin "P5") (pinfunction "CLK_P5") (pintype "bidirectional"))
      (node (ref "TP10") (pin "TP") (pinfunction "TP_TP") (pintype "input"))
    )
    (net (code "45") (name "SCL") (class "Default")
      (node (ref "BAT-CHARG") (pin "7") (pinfunction "SCL_7") (pintype "input"))
      (node (ref "ESP32") (pin "20") (pinfunction "IO22_20") (pintype "bidirectional"))
      (node (ref "QWIIC") (pin "3") (pinfunction "3_3") (pintype "passive"))
      (node (ref "R2-PINH") (pin "1") (pinfunction "1_1") (pintype "passive"))
      (node (ref "RTC-MOD") (pin "16") (pinfunction "SCL_16") (pintype "input"))
      (node (ref "SENSOR") (pin "4") (pinfunction "SCK_4") (pintype "input"))
    )
    (net (code "46") (name "SDA") (class "Default")
      (node (ref "BAT-CHARG") (pin "8") (pinfunction "SDA_8") (pintype "bidirectional"))
      (node (ref "ESP32") (pin "19") (pinfunction "IO21_19") (pintype "bidirectional"))
      (node (ref "QWIIC") (pin "4") (pinfunction "4_4") (pintype "passive"))
      (node (ref "R1_PINH") (pin "1") (pinfunction "1_1") (pintype "passive"))
      (node (ref "RTC-MOD") (pin "15") (pinfunction "SDA_15") (pintype "bidirectional"))
      (node (ref "SENSOR") (pin "3") (pinfunction "SDI_3") (pintype "bidirectional"))
    )
    (net (code "47") (name "SRC") (class "Default")
      (node (ref "C-EPAP-DRIV1") (pin "2") (pinfunction "2_2") (pintype "passive"))
      (node (ref "D-EPAP-DRIV2") (pin "2") (pinfunction "A_2") (pintype "bidirectional"))
      (node (ref "L2") (pin "1") (pinfunction "1_1") (pintype "passive"))
      (node (ref "Q-EPAP-DRIV") (pin "3") (pinfunction "D_3") (pintype "bidirectional"))
    )
    (net (code "48") (name "SS_SD") (class "Default")
      (node (ref "DSPI5") (pin "2") (pinfunction "2_2") (pintype "passive"))
      (node (ref "ESP32") (pin "4") (pinfunction "IO4_4") (pintype "bidirectional"))
      (node (ref "RSPI5") (pin "1") (pinfunction "1_1") (pintype "passive"))
      (node (ref "SD-CARD") (pin "P2") (pinfunction "CD/DAT3_P2") (pintype "bidirectional"))
    )
    (net (code "49") (name "TX") (class "Default")
      (node (ref "ESP32") (pin "25") (pinfunction "TXD0/GPIO16_25") (pintype "bidirectional"))
      (node (ref "TP1") (pin "TP") (pinfunction "TP_TP") (pintype "input"))
    )
    (net (code "50") (name "USB_D+") (class "Default")
      (node (ref "ESP32") (pin "14") (pinfunction "IO13_14") (pintype "bidirectional"))
      (node (ref "USBC-ESD") (pin "4") (pinfunction "I/O2_2_4") (pintype "bidirectional"))
    )
    (net (code "51") (name "USB_D-") (class "Default")
      (node (ref "ESP32") (pin "13") (pinfunction "IO12_13") (pintype "bidirectional"))
      (node (ref "USBC-ESD") (pin "6") (pinfunction "I/O1_2_6") (pintype "bidirectional"))
    )
    (net (code "52") (name "VBAT") (class "Default")
      (node (ref "BAT-CHARG") (pin "2") (pinfunction "CELL_2") (pintype "power_in"))
      (node (ref "BAT-CHARG") (pin "3") (pinfunction "VDD_3") (pintype "power_in"))
      (node (ref "C-LIPO") (pin "1") (pinfunction "1_1") (pintype "passive"))
      (node (ref "LIPO-CONTR") (pin "3") (pinfunction "VBAT_3") (pintype "power_in"))
      (node (ref "Q-LDO") (pin "3") (pinfunction "D_3") (pintype "bidirectional"))
      (node (ref "TP3") (pin "TP") (pinfunction "TP_TP") (pintype "input"))
    )
    (net (code "53") (name "VBUS") (class "Default")
      (node (ref "C-LIPO1") (pin "1") (pinfunction "1_1") (pintype "passive"))
      (node (ref "C-USBC-ESD") (pin "1") (pinfunction "1_1") (pintype "passive"))
      (node (ref "C-USBC-ESD1") (pin "1") (pinfunction "1_1") (pintype "passive"))
      (node (ref "CHG_LED") (pin "A") (pinfunction "A_A") (pintype "passive"))
      (node (ref "D-LDO") (pin "2") (pinfunction "ANODE_2") (pintype "bidirectional"))
      (node (ref "LIPO-CONTR") (pin "4") (pinfunction "VIN_4") (pintype "power_in"))
      (node (ref "PFMF.050.1") (pin "2") (pinfunction "2_2") (pintype "passive"))
      (node (ref "Q-LDO") (pin "1") (pinfunction "G_1") (pintype "bidirectional"))
      (node (ref "R-LDO") (pin "2") (pinfunction "2_2") (pintype "passive"))
      (node (ref "TP16") (pin "TP") (pinfunction "TP_TP") (pintype "input"))
      (node (ref "USBC-ESD") (pin "2") (pinfunction "GND_2") (pintype "bidirectional"))
    )
    (net (code "54") (name "VRTC") (class "Default")
      (node (ref "C-RTC") (pin "1") (pinfunction "1_1") (pintype "passive"))
      (node (ref "CPH3225A") (pin "1") (pinfunction "1_1") (pintype "passive"))
      (node (ref "R-RTC-CAP") (pin "1") (pinfunction "1_1") (pintype "passive"))
      (node (ref "RTC-MOD") (pin "14") (pinfunction "VBAT_14") (pintype "power_in"))
    )
    (net (code "55") (name "VUSB") (class "Default")
      (node (ref "PFMF.050.1") (pin "1") (pinfunction "1_1") (pintype "passive"))
      (node (ref "USBC-ESD1") (pin "A4") (pinfunction "A4_A4") (pintype "bidirectional"))
      (node (ref "USBC-ESD1") (pin "A9") (pinfunction "A9_A9") (pintype "bidirectional"))
      (node (ref "USBC-ESD1") (pin "B4") (pinfunction "B4_B4") (pintype "bidirectional"))
      (node (ref "USBC-ESD1") (pin "B9") (pinfunction "B9_B9") (pintype "bidirectional"))
    )
    (net (code "56") (name "unconnected-(BAT-CHARG-~{ALERT}-Pad5)") (class "Default")
      (node (ref "BAT-CHARG") (pin "5") (pinfunction "~{ALERT}_5") (pintype "output"))
    )
    (net (code "57") (name "unconnected-(EPAPER-DISPL-Pad1)") (class "Default")
      (node (ref "EPAPER-DISPL") (pin "1") (pinfunction "1_1") (pintype "bidirectional"))
    )
    (net (code "58") (name "unconnected-(EPAPER-DISPL-Pad6)") (class "Default")
      (node (ref "EPAPER-DISPL") (pin "6") (pinfunction "6_6") (pintype "bidirectional"))
    )
    (net (code "59") (name "unconnected-(EPAPER-DISPL-Pad7)") (class "Default")
      (node (ref "EPAPER-DISPL") (pin "7") (pinfunction "7_7") (pintype "bidirectional"))
    )
    (net (code "60") (name "unconnected-(ESP32-NC-Pad22)") (class "Default")
      (node (ref "ESP32") (pin "22") (pinfunction "NC_22") (pintype "no_connect"))
    )
    (net (code "61") (name "unconnected-(LDO-VR-NC-Pad4)") (class "Default")
      (node (ref "LDO-VR") (pin "4") (pinfunction "NC_4") (pintype "no_connect"))
    )
    (net (code "62") (name "unconnected-(SD-CARD-DAT1-PadP8)") (class "Default")
      (node (ref "SD-CARD") (pin "P8") (pinfunction "DAT1_P8") (pintype "bidirectional"))
    )
    (net (code "63") (name "unconnected-(SD-CARD-DAT2-PadP1)") (class "Default")
      (node (ref "SD-CARD") (pin "P1") (pinfunction "DAT2_P1") (pintype "bidirectional"))
    )
    (net (code "64") (name "unconnected-(SD-CARD-DETECTION_1-PadS1)") (class "Default")
      (node (ref "SD-CARD") (pin "S1") (pinfunction "DETECTION_1_S1") (pintype "bidirectional"))
    )
    (net (code "65") (name "unconnected-(SD-CARD-DETECTION_2-PadS2)") (class "Default")
      (node (ref "SD-CARD") (pin "S2") (pinfunction "DETECTION_2_S2") (pintype "bidirectional"))
    )
    (net (code "66") (name "unconnected-(USBC-ESD1-PadA8)") (class "Default")
      (node (ref "USBC-ESD1") (pin "A8") (pinfunction "A8_A8") (pintype "bidirectional"))
    )
    (net (code "67") (name "unconnected-(USBC-ESD1-PadB8)") (class "Default")
      (node (ref "USBC-ESD1") (pin "B8") (pinfunction "B8_B8") (pintype "bidirectional"))
    )
    (net (code "68") (name "unconnected-(VOL-SUPER-NC-Pad4)") (class "Default")
      (node (ref "VOL-SUPER") (pin "4") (pinfunction "NC_4") (pintype "no_connect"))
    )
  )
)
